# gardener.net
KiCad netlist of a schematic drawn in EAGLE
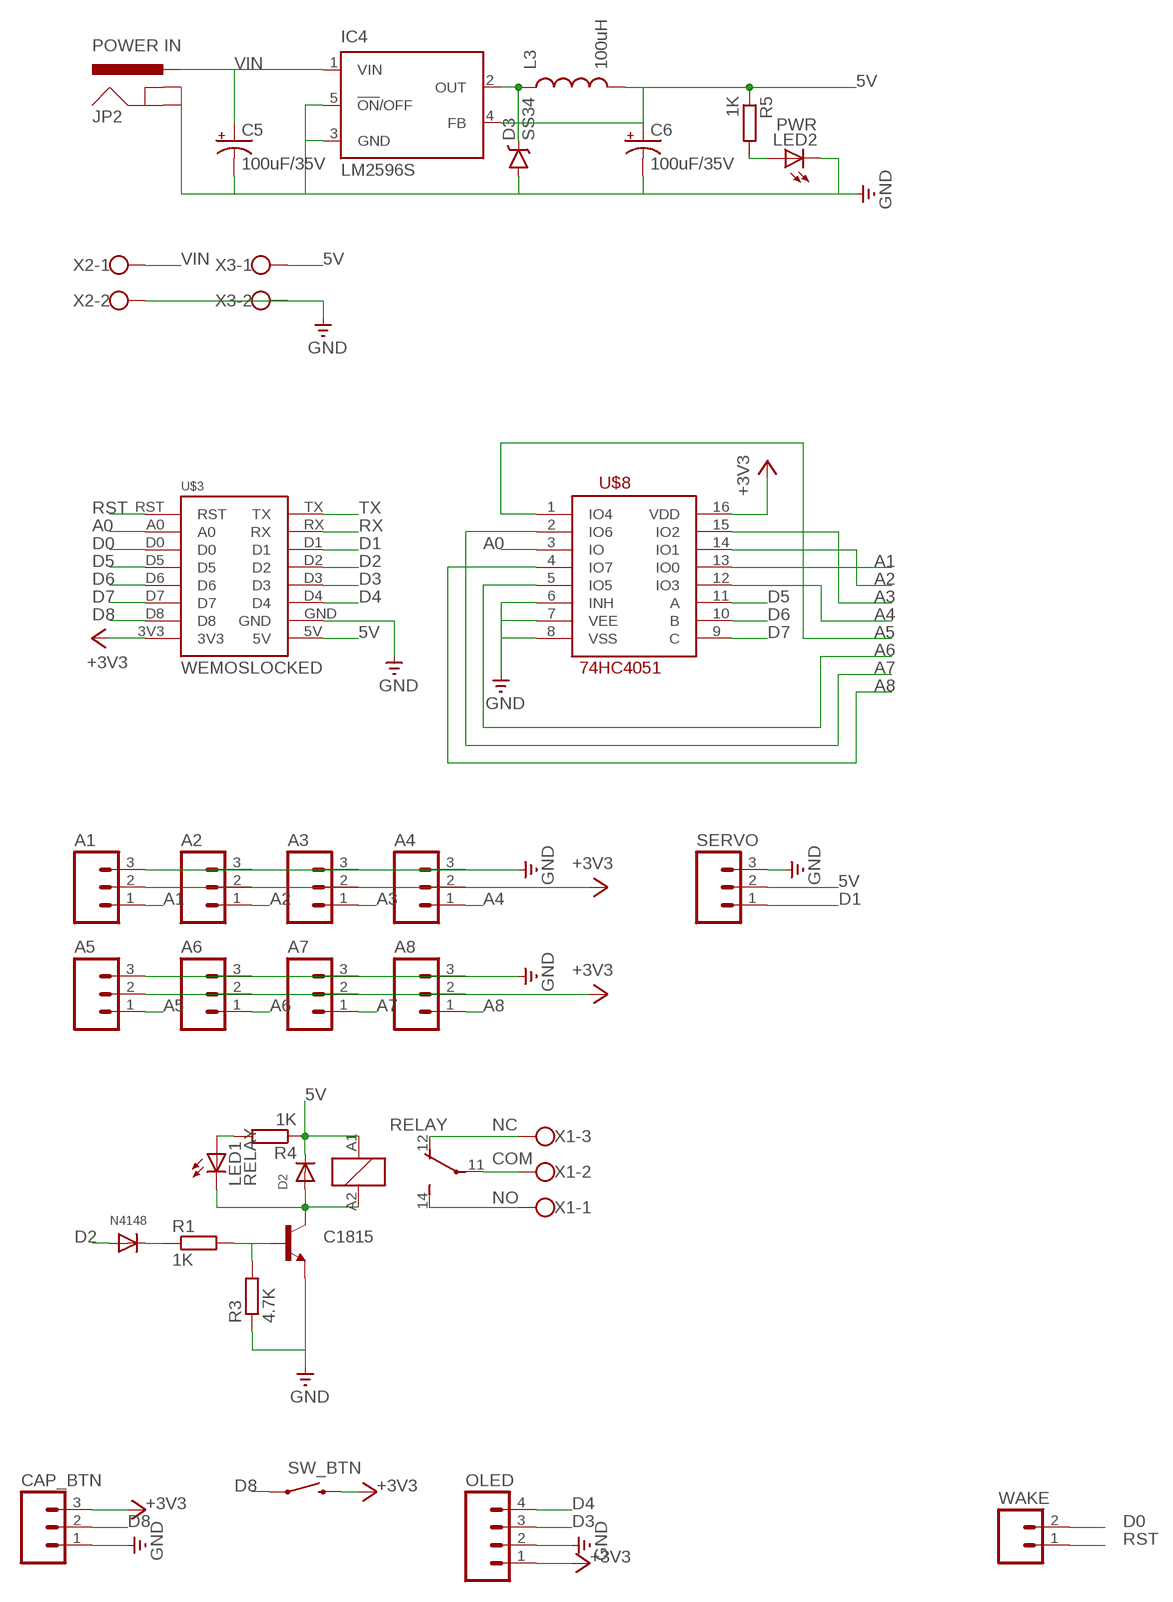
[diagram p0: schematic, sheet 1]

(export (version "E")
  (design (tool "Eeschema 10.0.6"))
  (components
    (comp (ref "A1")
      (value "M03PTH")
      (footprint "eagle-import:1X03")
      (libsource (lib "eagle-import") (part "M03PTH"))
    )
    (comp (ref "A2")
      (value "M03PTH")
      (footprint "eagle-import:1X03")
      (libsource (lib "eagle-import") (part "M03PTH"))
    )
    (comp (ref "A3")
      (value "M03PTH")
      (footprint "eagle-import:1X03")
      (libsource (lib "eagle-import") (part "M03PTH"))
    )
    (comp (ref "A4")
      (value "M03PTH")
      (footprint "eagle-import:1X03")
      (libsource (lib "eagle-import") (part "M03PTH"))
    )
    (comp (ref "A5")
      (value "M03PTH")
      (footprint "eagle-import:1X03")
      (libsource (lib "eagle-import") (part "M03PTH"))
    )
    (comp (ref "A6")
      (value "M03PTH")
      (footprint "eagle-import:1X03")
      (libsource (lib "eagle-import") (part "M03PTH"))
    )
    (comp (ref "A7")
      (value "M03PTH")
      (footprint "eagle-import:1X03")
      (libsource (lib "eagle-import") (part "M03PTH"))
    )
    (comp (ref "A8")
      (value "M03PTH")
      (footprint "eagle-import:1X03")
      (libsource (lib "eagle-import") (part "M03PTH"))
    )
    (comp (ref "C5")
      (value "100uF/35V")
      (footprint "eagle-import:PANASONIC_D")
      (libsource (lib "eagle-import") (part "CAP_POLD"))
    )
    (comp (ref "C6")
      (value "100uF/35V")
      (footprint "eagle-import:PANASONIC_D")
      (libsource (lib "eagle-import") (part "CAP_POLD"))
    )
    (comp (ref "C1815")
      (value "TRANSISTOR_NPNSOT23-3")
      (footprint "eagle-import:SOT23-3")
      (libsource (lib "eagle-import") (part "TRANSISTOR_NPNSOT23-3"))
    )
    (comp (ref "CAP_BTN")
      (value "M03PTH")
      (footprint "eagle-import:1X03")
      (libsource (lib "eagle-import") (part "M03PTH"))
    )
    (comp (ref "D2")
      (value "DIODESMA")
      (footprint "eagle-import:SMADIODE")
      (libsource (lib "eagle-import") (part "DIODESMA"))
    )
    (comp (ref "D3")
      (value "SS34")
      (footprint "eagle-import:SMA-DIODE")
      (libsource (lib "eagle-import") (part "MBRA140"))
    )
    (comp (ref "IC4")
      (value "LM2596S")
      (footprint "eagle-import:TO263-5")
      (fields (field (name "MF") "NATIONAL SEMICONDUCTOR") (field (name "MPN") "LM2596S-ADJ/NOPB"))
      (libsource (lib "eagle-import") (part "LM2596S"))
    )
    (comp (ref "JP2")
      (value "POWER IN")
      (footprint "eagle-import:POWER_JACK_PTH")
      (libsource (lib "eagle-import") (part "POWER_JACKPTH"))
    )
    (comp (ref "L3")
      (value "100uH")
      (footprint "eagle-import:INDUCTOR_SDR1307")
      (libsource (lib "eagle-import") (part "INDUCTORSDR13-7-270ML"))
    )
    (comp (ref "LED1")
      (value "RELAY")
      (footprint "eagle-import:LED3MM")
      (libsource (lib "eagle-import") (part "LED3MM"))
    )
    (comp (ref "LED2")
      (value "PWR")
      (footprint "eagle-import:LED3MM")
      (libsource (lib "eagle-import") (part "LED3MM"))
    )
    (comp (ref "N4148")
      (value "DIODESOD-123")
      (footprint "eagle-import:SOD-123")
      (libsource (lib "eagle-import") (part "DIODESOD-123"))
    )
    (comp (ref "OLED")
      (value "M04PTH")
      (footprint "eagle-import:1X04")
      (libsource (lib "eagle-import") (part "M04PTH"))
    )
    (comp (ref "R1")
      (value "1K")
      (footprint "eagle-import:R0805")
      (libsource (lib "eagle-import") (part "R-EU_R0805"))
    )
    (comp (ref "R3")
      (value "4.7K")
      (footprint "eagle-import:R0805")
      (libsource (lib "eagle-import") (part "R-EU_R0805"))
    )
    (comp (ref "R4")
      (value "1K")
      (footprint "eagle-import:R0805")
      (libsource (lib "eagle-import") (part "R-EU_R0805"))
    )
    (comp (ref "R5")
      (value "1K")
      (footprint "eagle-import:R0805")
      (libsource (lib "eagle-import") (part "R-EU_R0805"))
    )
    (comp (ref "RELAY")
      (value "ZNS5106")
      (footprint "eagle-import:ZN5")
      (libsource (lib "eagle-import") (part "ZNS5106"))
    )
    (comp (ref "SERVO")
      (value "M03PTH")
      (footprint "eagle-import:1X03")
      (libsource (lib "eagle-import") (part "M03PTH"))
    )
    (comp (ref "SW_BTN")
      (value "SWITCH-MOMENTARY-212MM")
      (footprint "eagle-import:TACTILE-PTH-12MM")
      (libsource (lib "eagle-import") (part "SWITCH-MOMENTARY-212MM"))
    )
    (comp (ref "U$3")
      (value "WEMOSLOCKED")
      (footprint "eagle-import:WEMOS_LOCKED")
      (libsource (lib "eagle-import") (part "WEMOSLOCKED"))
    )
    (comp (ref "U$8")
      (value "74HC4051")
      (footprint "eagle-import:74HC4051")
      (libsource (lib "eagle-import") (part "74HC4051"))
    )
    (comp (ref "WAKE")
      (value "M02PTH")
      (footprint "eagle-import:1X02")
      (libsource (lib "eagle-import") (part "M02PTH"))
    )
    (comp (ref "X1")
      (value "W237-103")
      (footprint "eagle-import:W237-103")
      (fields (field (name "MPN") "237-103"))
      (libsource (lib "eagle-import") (part "W237-103"))
    )
    (comp (ref "X2")
      (value "W237-102")
      (footprint "eagle-import:W237-102")
      (fields (field (name "MPN") "237-102"))
      (libsource (lib "eagle-import") (part "W237-102"))
    )
    (comp (ref "X3")
      (value "W237-102")
      (footprint "eagle-import:W237-102")
      (fields (field (name "MPN") "237-102"))
      (libsource (lib "eagle-import") (part "W237-102"))
    )
  )
  (nets
    (net (code "1") (name "+3V3") (class "Default")
      (node (ref "A1") (pin "2") (pinfunction "2_2") (pintype "passive"))
      (node (ref "A2") (pin "2") (pinfunction "2_2") (pintype "passive"))
      (node (ref "A3") (pin "2") (pinfunction "2_2") (pintype "passive"))
      (node (ref "A4") (pin "2") (pinfunction "2_2") (pintype "passive"))
      (node (ref "A5") (pin "2") (pinfunction "2_2") (pintype "passive"))
      (node (ref "A6") (pin "2") (pinfunction "2_2") (pintype "passive"))
      (node (ref "A7") (pin "2") (pinfunction "2_2") (pintype "passive"))
      (node (ref "A8") (pin "2") (pinfunction "2_2") (pintype "passive"))
      (node (ref "CAP_BTN") (pin "3") (pinfunction "3_3") (pintype "passive"))
      (node (ref "OLED") (pin "1") (pinfunction "1_1") (pintype "passive"))
      (node (ref "SW_BTN") (pin "3") (pinfunction "2_3") (pintype "passive"))
      (node (ref "U$3") (pin "3V3") (pinfunction "3V3_3V3") (pintype "bidirectional"))
      (node (ref "U$8") (pin "16") (pinfunction "VDD_16") (pintype "bidirectional"))
    )
    (net (code "2") (name "/5V") (class "Default")
      (node (ref "C6") (pin "+") (pinfunction "+_+") (pintype "passive"))
      (node (ref "D2") (pin "C") (pinfunction "C_C") (pintype "passive"))
      (node (ref "IC4") (pin "4") (pinfunction "FB_4") (pintype "input"))
      (node (ref "L3") (pin "P$2") (pinfunction "2_P$2") (pintype "passive"))
      (node (ref "R4") (pin "1") (pinfunction "1_1") (pintype "passive"))
      (node (ref "R5") (pin "1") (pinfunction "1_1") (pintype "passive"))
      (node (ref "RELAY") (pin "A1") (pinfunction "1_A1") (pintype "passive"))
      (node (ref "SERVO") (pin "2") (pinfunction "2_2") (pintype "passive"))
      (node (ref "U$3") (pin "5V") (pinfunction "5V_5V") (pintype "bidirectional"))
      (node (ref "X3") (pin "1") (pinfunction "KL_1") (pintype "passive"))
    )
    (net (code "3") (name "/A0") (class "Default")
      (node (ref "U$3") (pin "A0") (pinfunction "A0_A0") (pintype "bidirectional"))
      (node (ref "U$8") (pin "3") (pinfunction "IO_3") (pintype "bidirectional"))
    )
    (net (code "4") (name "/A1") (class "Default")
      (node (ref "A1") (pin "1") (pinfunction "1_1") (pintype "passive"))
      (node (ref "U$8") (pin "13") (pinfunction "IO0_13") (pintype "bidirectional"))
    )
    (net (code "5") (name "/A2") (class "Default")
      (node (ref "A2") (pin "1") (pinfunction "1_1") (pintype "passive"))
      (node (ref "U$8") (pin "14") (pinfunction "IO1_14") (pintype "bidirectional"))
    )
    (net (code "6") (name "/A3") (class "Default")
      (node (ref "A3") (pin "1") (pinfunction "1_1") (pintype "passive"))
      (node (ref "U$8") (pin "15") (pinfunction "IO2_15") (pintype "bidirectional"))
    )
    (net (code "7") (name "/A4") (class "Default")
      (node (ref "A4") (pin "1") (pinfunction "1_1") (pintype "passive"))
      (node (ref "U$8") (pin "12") (pinfunction "IO3_12") (pintype "bidirectional"))
    )
    (net (code "8") (name "/A5") (class "Default")
      (node (ref "A5") (pin "1") (pinfunction "1_1") (pintype "passive"))
      (node (ref "U$8") (pin "1") (pinfunction "IO4_1") (pintype "bidirectional"))
    )
    (net (code "9") (name "/A6") (class "Default")
      (node (ref "A6") (pin "1") (pinfunction "1_1") (pintype "passive"))
      (node (ref "U$8") (pin "5") (pinfunction "IO5_5") (pintype "bidirectional"))
    )
    (net (code "10") (name "/A7") (class "Default")
      (node (ref "A7") (pin "1") (pinfunction "1_1") (pintype "passive"))
      (node (ref "U$8") (pin "2") (pinfunction "IO6_2") (pintype "bidirectional"))
    )
    (net (code "11") (name "/A8") (class "Default")
      (node (ref "A8") (pin "1") (pinfunction "1_1") (pintype "passive"))
      (node (ref "U$8") (pin "4") (pinfunction "IO7_4") (pintype "bidirectional"))
    )
    (net (code "12") (name "/COM") (class "Default")
      (node (ref "RELAY") (pin "11") (pinfunction "P_11") (pintype "passive"))
      (node (ref "X1") (pin "2") (pinfunction "KL_2") (pintype "passive"))
    )
    (net (code "13") (name "/D0") (class "Default")
      (node (ref "U$3") (pin "D0") (pinfunction "D0_D0") (pintype "bidirectional"))
      (node (ref "WAKE") (pin "2") (pinfunction "2_2") (pintype "passive"))
    )
    (net (code "14") (name "/D1") (class "Default")
      (node (ref "SERVO") (pin "1") (pinfunction "1_1") (pintype "passive"))
      (node (ref "U$3") (pin "D1") (pinfunction "D1_D1") (pintype "bidirectional"))
    )
    (net (code "15") (name "/D2") (class "Default")
      (node (ref "N4148") (pin "A") (pinfunction "A_A") (pintype "passive"))
      (node (ref "U$3") (pin "D2") (pinfunction "D2_D2") (pintype "bidirectional"))
    )
    (net (code "16") (name "/D3") (class "Default")
      (node (ref "OLED") (pin "3") (pinfunction "3_3") (pintype "passive"))
      (node (ref "U$3") (pin "D3") (pinfunction "D3_D3") (pintype "bidirectional"))
    )
    (net (code "17") (name "/D4") (class "Default")
      (node (ref "OLED") (pin "4") (pinfunction "4_4") (pintype "passive"))
      (node (ref "U$3") (pin "D4") (pinfunction "D4_D4") (pintype "bidirectional"))
    )
    (net (code "18") (name "/D5") (class "Default")
      (node (ref "U$3") (pin "D5") (pinfunction "D5_D5") (pintype "bidirectional"))
      (node (ref "U$8") (pin "11") (pinfunction "A_11") (pintype "bidirectional"))
    )
    (net (code "19") (name "/D6") (class "Default")
      (node (ref "U$3") (pin "D6") (pinfunction "D6_D6") (pintype "bidirectional"))
      (node (ref "U$8") (pin "10") (pinfunction "B_10") (pintype "bidirectional"))
    )
    (net (code "20") (name "/D7") (class "Default")
      (node (ref "U$3") (pin "D7") (pinfunction "D7_D7") (pintype "bidirectional"))
      (node (ref "U$8") (pin "9") (pinfunction "C_9") (pintype "bidirectional"))
    )
    (net (code "21") (name "/D8") (class "Default")
      (node (ref "CAP_BTN") (pin "2") (pinfunction "2_2") (pintype "passive"))
      (node (ref "SW_BTN") (pin "1") (pinfunction "1_1") (pintype "passive"))
      (node (ref "U$3") (pin "D8") (pinfunction "D8_D8") (pintype "bidirectional"))
    )
    (net (code "22") (name "/NC") (class "Default")
      (node (ref "RELAY") (pin "12") (pinfunction "O_12") (pintype "passive"))
      (node (ref "X1") (pin "3") (pinfunction "KL_3") (pintype "passive"))
    )
    (net (code "23") (name "/NO") (class "Default")
      (node (ref "RELAY") (pin "14") (pinfunction "S_14") (pintype "passive"))
      (node (ref "X1") (pin "1") (pinfunction "KL_1") (pintype "passive"))
    )
    (net (code "24") (name "/RST") (class "Default")
      (node (ref "U$3") (pin "RST") (pinfunction "RST_RST") (pintype "bidirectional"))
      (node (ref "WAKE") (pin "1") (pinfunction "1_1") (pintype "passive"))
    )
    (net (code "25") (name "/RX") (class "Default")
      (node (ref "U$3") (pin "RX") (pinfunction "RX_RX") (pintype "bidirectional"))
    )
    (net (code "26") (name "/TX") (class "Default")
      (node (ref "U$3") (pin "TX") (pinfunction "TX_TX") (pintype "bidirectional"))
    )
    (net (code "27") (name "/VIN") (class "Default")
      (node (ref "C5") (pin "+") (pinfunction "+_+") (pintype "passive"))
      (node (ref "IC4") (pin "1") (pinfunction "VIN_1") (pintype "input"))
      (node (ref "JP2") (pin "PWR") (pinfunction "PWR_PWR") (pintype "bidirectional"))
      (node (ref "X2") (pin "1") (pinfunction "KL_1") (pintype "passive"))
    )
    (net (code "28") (name "GND") (class "Default")
      (node (ref "A1") (pin "3") (pinfunction "3_3") (pintype "passive"))
      (node (ref "A2") (pin "3") (pinfunction "3_3") (pintype "passive"))
      (node (ref "A3") (pin "3") (pinfunction "3_3") (pintype "passive"))
      (node (ref "A4") (pin "3") (pinfunction "3_3") (pintype "passive"))
      (node (ref "A5") (pin "3") (pinfunction "3_3") (pintype "passive"))
      (node (ref "A6") (pin "3") (pinfunction "3_3") (pintype "passive"))
      (node (ref "A7") (pin "3") (pinfunction "3_3") (pintype "passive"))
      (node (ref "A8") (pin "3") (pinfunction "3_3") (pintype "passive"))
      (node (ref "C1815") (pin "2") (pinfunction "E_2") (pintype "passive"))
      (node (ref "C5") (pin "-") (pinfunction "-_-") (pintype "passive"))
      (node (ref "C6") (pin "-") (pinfunction "-_-") (pintype "passive"))
      (node (ref "CAP_BTN") (pin "1") (pinfunction "1_1") (pintype "passive"))
      (node (ref "D3") (pin "A") (pinfunction "A_A") (pintype "passive"))
      (node (ref "IC4") (pin "3") (pinfunction "GND_3") (pintype "power_in"))
      (node (ref "IC4") (pin "5") (pinfunction "~{ON}/OFF_5") (pintype "input"))
      (node (ref "JP2") (pin "GND") (pinfunction "GND_GND") (pintype "bidirectional"))
      (node (ref "JP2") (pin "GNDBREAK") (pinfunction "GNDBREAK_GNDBREAK") (pintype "bidirectional"))
      (node (ref "LED2") (pin "K") (pinfunction "C_K") (pintype "passive"))
      (node (ref "OLED") (pin "2") (pinfunction "2_2") (pintype "passive"))
      (node (ref "R3") (pin "1") (pinfunction "1_1") (pintype "passive"))
      (node (ref "SERVO") (pin "3") (pinfunction "3_3") (pintype "passive"))
      (node (ref "U$3") (pin "GND") (pinfunction "GND_GND") (pintype "bidirectional"))
      (node (ref "U$8") (pin "6") (pinfunction "INH_6") (pintype "bidirectional"))
      (node (ref "U$8") (pin "7") (pinfunction "VEE_7") (pintype "bidirectional"))
      (node (ref "U$8") (pin "8") (pinfunction "VSS_8") (pintype "bidirectional"))
      (node (ref "X2") (pin "2") (pinfunction "KL_2") (pintype "passive"))
      (node (ref "X3") (pin "2") (pinfunction "KL_2") (pintype "passive"))
    )
    (net (code "29") (name "Net-(C1815-B)") (class "Default")
      (node (ref "C1815") (pin "1") (pinfunction "B_1") (pintype "passive"))
      (node (ref "R1") (pin "2") (pinfunction "2_2") (pintype "passive"))
      (node (ref "R3") (pin "2") (pinfunction "2_2") (pintype "passive"))
    )
    (net (code "30") (name "Net-(C1815-C)") (class "Default")
      (node (ref "C1815") (pin "3") (pinfunction "C_3") (pintype "passive"))
      (node (ref "D2") (pin "A") (pinfunction "A_A") (pintype "passive"))
      (node (ref "LED1") (pin "K") (pinfunction "C_K") (pintype "passive"))
      (node (ref "RELAY") (pin "A2") (pinfunction "2_A2") (pintype "passive"))
    )
    (net (code "31") (name "Net-(IC4-OUT)") (class "Default")
      (node (ref "D3") (pin "C") (pinfunction "C_C") (pintype "passive"))
      (node (ref "IC4") (pin "2") (pinfunction "OUT_2") (pintype "output"))
      (node (ref "L3") (pin "P$1") (pinfunction "1_P$1") (pintype "passive"))
    )
    (net (code "32") (name "Net-(LED1-PadA)") (class "Default")
      (node (ref "LED1") (pin "A") (pinfunction "A_A") (pintype "passive"))
      (node (ref "R4") (pin "2") (pinfunction "2_2") (pintype "passive"))
    )
    (net (code "33") (name "Net-(LED2-PadA)") (class "Default")
      (node (ref "LED2") (pin "A") (pinfunction "A_A") (pintype "passive"))
      (node (ref "R5") (pin "2") (pinfunction "2_2") (pintype "passive"))
    )
    (net (code "34") (name "Net-(N4148-PadC)") (class "Default")
      (node (ref "N4148") (pin "C") (pinfunction "C_C") (pintype "passive"))
      (node (ref "R1") (pin "1") (pinfunction "1_1") (pintype "passive"))
    )
  )
)
